# GPS.net
KiCad netlist of a schematic drawn in Altium Designer
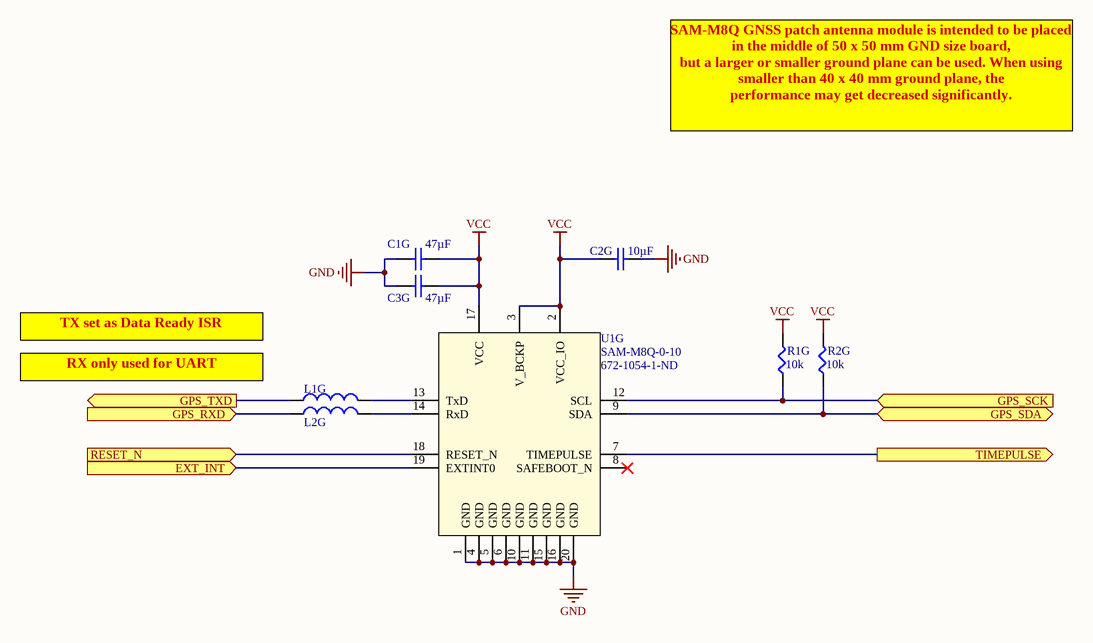
[diagram p0: GPS.SchDoc]

(export (version "E")
  (design (tool "Eeschema 10.0.6"))
  (components
    (comp (ref "C1G")
      (value "GRM21BR61A476ME15L")
      (footprint "C0805N")
      (description "47µF 10V Ceramic Capacitor X5R 0805")
      (fields
        (field (name "HOUSEPART") "NO")
        (field (name "TOLERANCE") "±20%")
        (field (name "CAPACITANCE") "47µF")
      )
      (libsource (lib "MF_Passives") (part "CAPACITOR_NP"))
    )
    (comp (ref "C2G")
      (value "GRT188R61C106KE13D")
      (footprint "C0603N")
      (description "10µF 16V Ceramic Capacitor X5R 0603")
      (fields
        (field (name "HOUSEPART") "NO")
        (field (name "TOLERANCE") "±10%")
        (field (name "CAPACITANCE") "10µF")
      )
      (libsource (lib "MF_Passives") (part "CAPACITOR_NP"))
    )
    (comp (ref "C3G")
      (value "GRM21BR61A476ME15L")
      (footprint "C0805N")
      (description "47µF 10V Ceramic Capacitor X5R 0805")
      (fields
        (field (name "HOUSEPART") "NO")
        (field (name "TOLERANCE") "±20%")
        (field (name "CAPACITANCE") "47µF")
      )
      (libsource (lib "MF_Passives") (part "CAPACITOR_NP"))
    )
    (comp (ref "L1G")
      (value "LI0603G221R-10")
      (footprint "R0603L")
      (fields (field (name "HOUSEPART") "NO"))
      (libsource (lib "MF_Passives") (part "INDUCTOR"))
    )
    (comp (ref "L2G")
      (value "LI0603G221R-10")
      (footprint "R0603L")
      (fields (field (name "HOUSEPART") "NO"))
      (libsource (lib "MF_Passives") (part "INDUCTOR"))
    )
    (comp (ref "R1G")
      (value "10k")
      (footprint "SMD-0603-RES")
      (description "RES SMD 10K OHM 1% 1/10W 0603")
      (fields
        (field (name "PART NUMBER") "ERJ-3EKF1002V")
        (field (name "DIGI-KEY PART NUMBER") "P10.0KHCT-ND")
      )
      (libsource (lib "Panasonic_ERJ_0603") (part "ERJ-3EKF1002V"))
    )
    (comp (ref "R2G")
      (value "10k")
      (footprint "SMD-0603-RES")
      (description "RES SMD 10K OHM 1% 1/10W 0603")
      (fields
        (field (name "PART NUMBER") "ERJ-3EKF1002V")
        (field (name "DIGI-KEY PART NUMBER") "P10.0KHCT-ND")
      )
      (libsource (lib "Panasonic_ERJ_0603") (part "ERJ-3EKF1002V"))
    )
    (comp (ref "U1G")
      (value "SAM-M8Q-0-10")
      (footprint "SAM-M8Q")
      (description "u-Blox M8 Gnss Antenna Module Tc")
      (fields (field (name "SUPPLIER PART NUMBER 1") "672-1054-1-ND"))
      (libsource (lib "ublox") (part "ublox-sam-m8Q"))
    )
  )
  (nets
    (net (code "1") (name "/EXT_INT") (class "Default")
      (node (ref "U1G") (pin "19") (pinfunction "EXTINT0_19") (pintype "passive"))
    )
    (net (code "2") (name "/GPS_RXD") (class "Default")
      (node (ref "L2G") (pin "1") (pinfunction "1_1") (pintype "passive"))
    )
    (net (code "3") (name "/GPS_SCK") (class "Default")
      (node (ref "R1G") (pin "1") (pinfunction "1_1") (pintype "passive"))
      (node (ref "U1G") (pin "12") (pinfunction "SCL_12") (pintype "passive"))
    )
    (net (code "4") (name "/GPS_SDA") (class "Default")
      (node (ref "R2G") (pin "1") (pinfunction "1_1") (pintype "passive"))
      (node (ref "U1G") (pin "9") (pinfunction "SDA_9") (pintype "passive"))
    )
    (net (code "5") (name "/GPS_TXD") (class "Default")
      (node (ref "L1G") (pin "1") (pinfunction "1_1") (pintype "passive"))
    )
    (net (code "6") (name "/RESET_N") (class "Default")
      (node (ref "U1G") (pin "18") (pinfunction "RESET_N_18") (pintype "passive"))
    )
    (net (code "7") (name "/TIMEPULSE") (class "Default")
      (node (ref "U1G") (pin "7") (pinfunction "TIMEPULSE_7") (pintype "passive"))
    )
    (net (code "8") (name "GND") (class "Default")
      (node (ref "C1G") (pin "2") (pinfunction "2_2") (pintype "passive"))
      (node (ref "C2G") (pin "2") (pinfunction "2_2") (pintype "passive"))
      (node (ref "C3G") (pin "2") (pinfunction "2_2") (pintype "passive"))
      (node (ref "U1G") (pin "1") (pinfunction "GND_1") (pintype "passive"))
      (node (ref "U1G") (pin "10") (pinfunction "GND_10") (pintype "passive"))
      (node (ref "U1G") (pin "11") (pinfunction "GND_11") (pintype "passive"))
      (node (ref "U1G") (pin "15") (pinfunction "GND_15") (pintype "passive"))
      (node (ref "U1G") (pin "16") (pinfunction "GND_16") (pintype "passive"))
      (node (ref "U1G") (pin "20") (pinfunction "GND_20") (pintype "passive"))
      (node (ref "U1G") (pin "4") (pinfunction "GND_4") (pintype "passive"))
      (node (ref "U1G") (pin "5") (pinfunction "GND_5") (pintype "passive"))
      (node (ref "U1G") (pin "6") (pinfunction "GND_6") (pintype "passive"))
    )
    (net (code "9") (name "Net-(U1G-RxD)") (class "Default")
      (node (ref "L2G") (pin "2") (pinfunction "2_2") (pintype "passive"))
      (node (ref "U1G") (pin "14") (pinfunction "RxD_14") (pintype "passive"))
    )
    (net (code "10") (name "Net-(U1G-TxD)") (class "Default")
      (node (ref "L1G") (pin "2") (pinfunction "2_2") (pintype "passive"))
      (node (ref "U1G") (pin "13") (pinfunction "TxD_13") (pintype "passive"))
    )
    (net (code "11") (name "VCC") (class "Default")
      (node (ref "C1G") (pin "1") (pinfunction "1_1") (pintype "passive"))
      (node (ref "C2G") (pin "1") (pinfunction "1_1") (pintype "passive"))
      (node (ref "C3G") (pin "1") (pinfunction "1_1") (pintype "passive"))
      (node (ref "R1G") (pin "2") (pinfunction "2_2") (pintype "passive"))
      (node (ref "R2G") (pin "2") (pinfunction "2_2") (pintype "passive"))
      (node (ref "U1G") (pin "17") (pinfunction "VCC_17") (pintype "passive"))
      (node (ref "U1G") (pin "2") (pinfunction "VCC_IO_2") (pintype "passive"))
      (node (ref "U1G") (pin "3") (pinfunction "V_BCKP_3") (pintype "passive"))
    )
    (net (code "12") (name "unconnected-(U1G-SAFEBOOT_N-Pad8)") (class "Default")
      (node (ref "U1G") (pin "8") (pinfunction "SAFEBOOT_N_8") (pintype "passive+no_connect"))
    )
  )
)
